# E16-02-002.net
KiCad netlist of a schematic drawn in Altium Designer
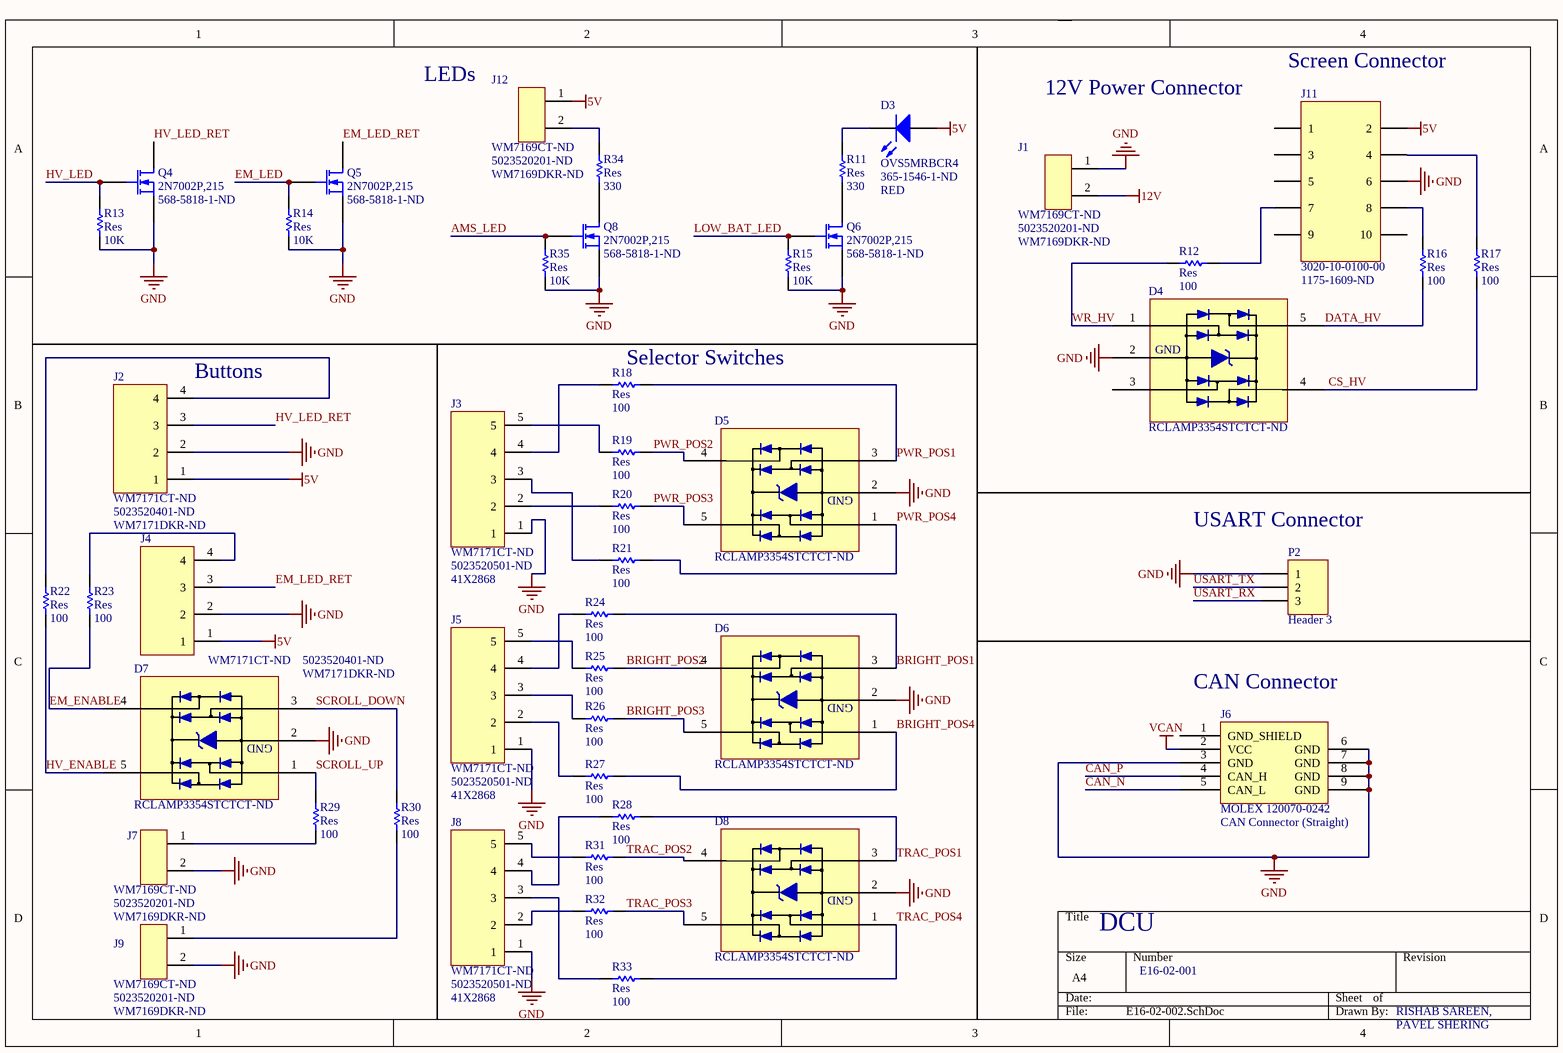
[diagram p0: E16-02-002.SchDoc]

(export (version "E")
  (design (tool "Eeschema 10.0.6"))
  (components
    (comp (ref "D3")
      (value "OVS5MRBCR4")
      (footprint "OVS5MRBCR4")
      (description "Typical RED LED")
      (fields
        (field (name "SUPPLIER PART NUMBER 1") "365-1546-1-ND")
        (field (name "COLOUR") "RED")
        (field (name "PUBLISHER") "Altium Limited")
      )
      (libsource (lib "LEDs") (part "OVS5MRBCR4"))
    )
    (comp (ref "D4")
      (value "RCLAMP3354S.TCT")
      (footprint "SOT95P280X145-5N")
      (description "TVS DIODE 3.3VWM 16VC")
      (fields (field (name "SUPPLIER PART NUMBER 1") "RCLAMP3354STCTCT-ND"))
      (libsource (lib "Diodes") (part "RCLAMP3354S.TCT"))
    )
    (comp (ref "D5")
      (value "RCLAMP3354S.TCT")
      (footprint "SOT95P280X145-5N")
      (description "TVS DIODE 3.3VWM 16VC")
      (fields (field (name "SUPPLIER PART NUMBER 1") "RCLAMP3354STCTCT-ND"))
      (libsource (lib "Diodes") (part "RCLAMP3354S.TCT"))
    )
    (comp (ref "D6")
      (value "RCLAMP3354S.TCT")
      (footprint "SOT95P280X145-5N")
      (description "TVS DIODE 3.3VWM 16VC")
      (fields (field (name "SUPPLIER PART NUMBER 1") "RCLAMP3354STCTCT-ND"))
      (libsource (lib "Diodes") (part "RCLAMP3354S.TCT"))
    )
    (comp (ref "D7")
      (value "RCLAMP3354S.TCT")
      (footprint "SOT95P280X145-5N")
      (description "TVS DIODE 3.3VWM 16VC")
      (fields (field (name "SUPPLIER PART NUMBER 1") "RCLAMP3354STCTCT-ND"))
      (libsource (lib "Diodes") (part "RCLAMP3354S.TCT"))
    )
    (comp (ref "D8")
      (value "RCLAMP3354S.TCT")
      (footprint "SOT95P280X145-5N")
      (description "TVS DIODE 3.3VWM 16VC")
      (fields (field (name "SUPPLIER PART NUMBER 1") "RCLAMP3354STCTCT-ND"))
      (libsource (lib "Diodes") (part "RCLAMP3354S.TCT"))
    )
    (comp (ref "J1")
      (value "J_5023520200")
      (footprint "MOLEX_DURACLIK_2")
      (description "MOLEX DURACLIK 2-PIN RA")
      (fields
        (field (name "SUPPLIER PART NUMBER 1") "5023520201-ND")
        (field (name "SUPPLIER PART NUMBER 2") "WM7169DKR-ND")
      )
      (libsource (lib "Molex_DuraClik") (part "J_5023520200"))
    )
    (comp (ref "J2")
      (value "WM7171CT-ND")
      (footprint "MOLEX_DURACLIK_4")
      (description "MOLEX DURACLIK 4-PIN RA")
      (fields
        (field (name "DIGIKEY_PN") "WM7171CT-ND")
        (field (name "SUPPLIER PART NUMBER 1") "5023520401-ND")
        (field (name "SUPPLIER PART NUMBER 2") "WM7171DKR-ND")
      )
      (libsource (lib "Molex_DuraClik") (part "J_5023520400"))
    )
    (comp (ref "J3")
      (value "WM7171CT-ND")
      (footprint "MOLEX_DURACLIK_5")
      (description "MOLEX DURACLIK 5-PIN RA")
      (fields
        (field (name "DIGIKEY_PN") "WM7171CT-ND")
        (field (name "SUPPLIER PART NUMBER 1") "5023520501-ND")
        (field (name "SUPPLIER PART NUMBER 2") "41X2868")
      )
      (libsource (lib "Molex_DuraClik") (part "J_5023520500"))
    )
    (comp (ref "J4")
      (value "WM7171CT-ND")
      (footprint "MOLEX_DURACLIK_4")
      (description "MOLEX DURACLIK 4-PIN RA")
      (fields
        (field (name "DIGIKEY_PN") "WM7171CT-ND")
        (field (name "SUPPLIER PART NUMBER 1") "5023520401-ND")
        (field (name "SUPPLIER PART NUMBER 2") "WM7171DKR-ND")
      )
      (libsource (lib "Molex_DuraClik") (part "J_5023520400"))
    )
    (comp (ref "J5")
      (value "WM7171CT-ND")
      (footprint "MOLEX_DURACLIK_5")
      (description "MOLEX DURACLIK 5-PIN RA")
      (fields
        (field (name "DIGIKEY_PN") "WM7171CT-ND")
        (field (name "SUPPLIER PART NUMBER 1") "5023520501-ND")
        (field (name "SUPPLIER PART NUMBER 2") "41X2868")
      )
      (libsource (lib "Molex_DuraClik") (part "J_5023520500"))
    )
    (comp (ref "J6")
      (value "CAN Connector (Straight)")
      (footprint "CAN Connector (Straight)")
      (libsource (lib "Molex_CAN_Connector") (part "CAN Connector (Straight)"))
    )
    (comp (ref "J7")
      (value "J_5023520200")
      (footprint "MOLEX_DURACLIK_2")
      (description "MOLEX DURACLIK 2-PIN RA")
      (fields
        (field (name "SUPPLIER PART NUMBER 1") "5023520201-ND")
        (field (name "SUPPLIER PART NUMBER 2") "WM7169DKR-ND")
      )
      (libsource (lib "Molex_DuraClik") (part "J_5023520200"))
    )
    (comp (ref "J8")
      (value "WM7171CT-ND")
      (footprint "MOLEX_DURACLIK_5")
      (description "MOLEX DURACLIK 5-PIN RA")
      (fields
        (field (name "DIGIKEY_PN") "WM7171CT-ND")
        (field (name "SUPPLIER PART NUMBER 1") "5023520501-ND")
        (field (name "SUPPLIER PART NUMBER 2") "41X2868")
      )
      (libsource (lib "Molex_DuraClik") (part "J_5023520500"))
    )
    (comp (ref "J9")
      (value "J_5023520200")
      (footprint "MOLEX_DURACLIK_2")
      (description "MOLEX DURACLIK 2-PIN RA")
      (fields
        (field (name "SUPPLIER PART NUMBER 1") "5023520201-ND")
        (field (name "SUPPLIER PART NUMBER 2") "WM7169DKR-ND")
      )
      (libsource (lib "Molex_DuraClik") (part "J_5023520200"))
    )
    (comp (ref "J11")
      (value "3020-10-0100-00")
      (footprint "IDC 10 Pos")
      (fields (field (name "SUPPLIER PART NUMBER 1") "1175-1609-ND"))
      (libsource (lib "Connectors and Headers") (part "IDC_10Pos"))
    )
    (comp (ref "J12")
      (value "J_5023520200")
      (footprint "MOLEX_DURACLIK_2")
      (description "MOLEX DURACLIK 2-PIN RA")
      (fields
        (field (name "SUPPLIER PART NUMBER 1") "5023520201-ND")
        (field (name "SUPPLIER PART NUMBER 2") "WM7169DKR-ND")
      )
      (libsource (lib "Molex_DuraClik") (part "J_5023520200"))
    )
    (comp (ref "P2")
      (value "Header 3")
      (footprint "HDR1X3")
      (description "Header, 3-Pin")
      (fields (field (name "PUBLISHER") "Altium Limited"))
      (libsource (lib "Connectors and Headers") (part "Header 3"))
    )
    (comp (ref "Q4")
      (value "2N7002P,215")
      (footprint "SOT23-3")
      (description "N-Channel Enhancement Mode Vertical DMOS FET")
      (fields (field (name "SUPPLIER PART NUMBER 1") "568-5818-1-ND"))
      (libsource (lib "Transistors") (part "2N7002P,215"))
    )
    (comp (ref "Q5")
      (value "2N7002P,215")
      (footprint "SOT23-3")
      (description "N-Channel Enhancement Mode Vertical DMOS FET")
      (fields (field (name "SUPPLIER PART NUMBER 1") "568-5818-1-ND"))
      (libsource (lib "Transistors") (part "2N7002P,215"))
    )
    (comp (ref "Q6")
      (value "2N7002P,215")
      (footprint "SOT23-3")
      (description "N-Channel Enhancement Mode Vertical DMOS FET")
      (fields (field (name "SUPPLIER PART NUMBER 1") "568-5818-1-ND"))
      (libsource (lib "Transistors") (part "2N7002P,215"))
    )
    (comp (ref "Q8")
      (value "2N7002P,215")
      (footprint "SOT23-3")
      (description "N-Channel Enhancement Mode Vertical DMOS FET")
      (fields (field (name "SUPPLIER PART NUMBER 1") "568-5818-1-ND"))
      (libsource (lib "Transistors") (part "2N7002P,215"))
    )
    (comp (ref "R11")
      (value "Res")
      (footprint "3216[1206]")
      (description "Surface Mount Resistor")
      (fields (field (name "ALTIUM_VALUE") "330") (field (name "PUBLISHER") "Altium Limited"))
      (libsource (lib "Resistors") (part "Res"))
    )
    (comp (ref "R12")
      (value "Res")
      (footprint "3216[1206]")
      (description "Surface Mount Resistor")
      (fields (field (name "ALTIUM_VALUE") "100") (field (name "PUBLISHER") "Altium Limited"))
      (libsource (lib "Resistors") (part "Res"))
    )
    (comp (ref "R13")
      (value "Res")
      (footprint "3216[1206]")
      (description "Surface Mount Resistor")
      (fields (field (name "ALTIUM_VALUE") "10K") (field (name "PUBLISHER") "Altium Limited"))
      (libsource (lib "Resistors") (part "Res"))
    )
    (comp (ref "R14")
      (value "Res")
      (footprint "3216[1206]")
      (description "Surface Mount Resistor")
      (fields (field (name "ALTIUM_VALUE") "10K") (field (name "PUBLISHER") "Altium Limited"))
      (libsource (lib "Resistors") (part "Res"))
    )
    (comp (ref "R15")
      (value "Res")
      (footprint "3216[1206]")
      (description "Surface Mount Resistor")
      (fields (field (name "ALTIUM_VALUE") "10K") (field (name "PUBLISHER") "Altium Limited"))
      (libsource (lib "Resistors") (part "Res"))
    )
    (comp (ref "R16")
      (value "Res")
      (footprint "3216[1206]")
      (description "Surface Mount Resistor")
      (fields (field (name "ALTIUM_VALUE") "100") (field (name "PUBLISHER") "Altium Limited"))
      (libsource (lib "Resistors") (part "Res"))
    )
    (comp (ref "R17")
      (value "Res")
      (footprint "3216[1206]")
      (description "Surface Mount Resistor")
      (fields (field (name "ALTIUM_VALUE") "100") (field (name "PUBLISHER") "Altium Limited"))
      (libsource (lib "Resistors") (part "Res"))
    )
    (comp (ref "R18")
      (value "Res")
      (footprint "3216[1206]")
      (description "Surface Mount Resistor")
      (fields (field (name "ALTIUM_VALUE") "100") (field (name "PUBLISHER") "Altium Limited"))
      (libsource (lib "Resistors") (part "Res"))
    )
    (comp (ref "R19")
      (value "Res")
      (footprint "3216[1206]")
      (description "Surface Mount Resistor")
      (fields (field (name "ALTIUM_VALUE") "100") (field (name "PUBLISHER") "Altium Limited"))
      (libsource (lib "Resistors") (part "Res"))
    )
    (comp (ref "R20")
      (value "Res")
      (footprint "3216[1206]")
      (description "Surface Mount Resistor")
      (fields (field (name "ALTIUM_VALUE") "100") (field (name "PUBLISHER") "Altium Limited"))
      (libsource (lib "Resistors") (part "Res"))
    )
    (comp (ref "R21")
      (value "Res")
      (footprint "3216[1206]")
      (description "Surface Mount Resistor")
      (fields (field (name "ALTIUM_VALUE") "100") (field (name "PUBLISHER") "Altium Limited"))
      (libsource (lib "Resistors") (part "Res"))
    )
    (comp (ref "R22")
      (value "Res")
      (footprint "3216[1206]")
      (description "Surface Mount Resistor")
      (fields (field (name "ALTIUM_VALUE") "100") (field (name "PUBLISHER") "Altium Limited"))
      (libsource (lib "Resistors") (part "Res"))
    )
    (comp (ref "R23")
      (value "Res")
      (footprint "3216[1206]")
      (description "Surface Mount Resistor")
      (fields (field (name "ALTIUM_VALUE") "100") (field (name "PUBLISHER") "Altium Limited"))
      (libsource (lib "Resistors") (part "Res"))
    )
    (comp (ref "R24")
      (value "Res")
      (footprint "3216[1206]")
      (description "Surface Mount Resistor")
      (fields (field (name "ALTIUM_VALUE") "100") (field (name "PUBLISHER") "Altium Limited"))
      (libsource (lib "Resistors") (part "Res"))
    )
    (comp (ref "R25")
      (value "Res")
      (footprint "3216[1206]")
      (description "Surface Mount Resistor")
      (fields (field (name "ALTIUM_VALUE") "100") (field (name "PUBLISHER") "Altium Limited"))
      (libsource (lib "Resistors") (part "Res"))
    )
    (comp (ref "R26")
      (value "Res")
      (footprint "3216[1206]")
      (description "Surface Mount Resistor")
      (fields (field (name "ALTIUM_VALUE") "100") (field (name "PUBLISHER") "Altium Limited"))
      (libsource (lib "Resistors") (part "Res"))
    )
    (comp (ref "R27")
      (value "Res")
      (footprint "3216[1206]")
      (description "Surface Mount Resistor")
      (fields (field (name "ALTIUM_VALUE") "100") (field (name "PUBLISHER") "Altium Limited"))
      (libsource (lib "Resistors") (part "Res"))
    )
    (comp (ref "R28")
      (value "Res")
      (footprint "3216[1206]")
      (description "Surface Mount Resistor")
      (fields (field (name "ALTIUM_VALUE") "100") (field (name "PUBLISHER") "Altium Limited"))
      (libsource (lib "Resistors") (part "Res"))
    )
    (comp (ref "R29")
      (value "Res")
      (footprint "3216[1206]")
      (description "Surface Mount Resistor")
      (fields (field (name "ALTIUM_VALUE") "100") (field (name "PUBLISHER") "Altium Limited"))
      (libsource (lib "Resistors") (part "Res"))
    )
    (comp (ref "R30")
      (value "Res")
      (footprint "3216[1206]")
      (description "Surface Mount Resistor")
      (fields (field (name "ALTIUM_VALUE") "100") (field (name "PUBLISHER") "Altium Limited"))
      (libsource (lib "Resistors") (part "Res"))
    )
    (comp (ref "R31")
      (value "Res")
      (footprint "3216[1206]")
      (description "Surface Mount Resistor")
      (fields (field (name "ALTIUM_VALUE") "100") (field (name "PUBLISHER") "Altium Limited"))
      (libsource (lib "Resistors") (part "Res"))
    )
    (comp (ref "R32")
      (value "Res")
      (footprint "3216[1206]")
      (description "Surface Mount Resistor")
      (fields (field (name "ALTIUM_VALUE") "100") (field (name "PUBLISHER") "Altium Limited"))
      (libsource (lib "Resistors") (part "Res"))
    )
    (comp (ref "R33")
      (value "Res")
      (footprint "3216[1206]")
      (description "Surface Mount Resistor")
      (fields (field (name "ALTIUM_VALUE") "100") (field (name "PUBLISHER") "Altium Limited"))
      (libsource (lib "Resistors") (part "Res"))
    )
    (comp (ref "R34")
      (value "Res")
      (footprint "3216[1206]")
      (description "Surface Mount Resistor")
      (fields (field (name "ALTIUM_VALUE") "330") (field (name "PUBLISHER") "Altium Limited"))
      (libsource (lib "Resistors") (part "Res"))
    )
    (comp (ref "R35")
      (value "Res")
      (footprint "3216[1206]")
      (description "Surface Mount Resistor")
      (fields (field (name "ALTIUM_VALUE") "10K") (field (name "PUBLISHER") "Altium Limited"))
      (libsource (lib "Resistors") (part "Res"))
    )
  )
  (nets
    (net (code "1") (name "/AMS_LED") (class "Default")
      (node (ref "Q8") (pin "1") (pinfunction "G_1") (pintype "passive"))
      (node (ref "R35") (pin "2") (pinfunction "2_2") (pintype "passive"))
    )
    (net (code "2") (name "/BRIGHT_POS1") (class "Default")
      (node (ref "D6") (pin "3") (pinfunction "3_3") (pintype "passive"))
      (node (ref "R24") (pin "1") (pinfunction "1_1") (pintype "passive"))
    )
    (net (code "3") (name "/BRIGHT_POS2") (class "Default")
      (node (ref "D6") (pin "4") (pinfunction "4_4") (pintype "passive"))
      (node (ref "R25") (pin "2") (pinfunction "2_2") (pintype "passive"))
    )
    (net (code "4") (name "/BRIGHT_POS3") (class "Default")
      (node (ref "D6") (pin "5") (pinfunction "5_5") (pintype "passive"))
      (node (ref "R26") (pin "2") (pinfunction "2_2") (pintype "passive"))
    )
    (net (code "5") (name "/BRIGHT_POS4") (class "Default")
      (node (ref "D6") (pin "1") (pinfunction "1_1") (pintype "passive"))
      (node (ref "R27") (pin "1") (pinfunction "1_1") (pintype "passive"))
    )
    (net (code "6") (name "/CAN_N") (class "Default")
      (node (ref "J6") (pin "5") (pinfunction "CAN_L_5") (pintype "passive"))
    )
    (net (code "7") (name "/CAN_P") (class "Default")
      (node (ref "J6") (pin "4") (pinfunction "CAN_H_4") (pintype "passive"))
    )
    (net (code "8") (name "/CS_HV") (class "Default")
      (node (ref "D4") (pin "4") (pinfunction "4_4") (pintype "passive"))
      (node (ref "R17") (pin "1") (pinfunction "1_1") (pintype "passive"))
    )
    (net (code "9") (name "/DATA_HV") (class "Default")
      (node (ref "D4") (pin "5") (pinfunction "5_5") (pintype "passive"))
      (node (ref "R16") (pin "1") (pinfunction "1_1") (pintype "passive"))
    )
    (net (code "10") (name "/EM_ENABLE") (class "Default")
      (node (ref "D7") (pin "4") (pinfunction "4_4") (pintype "passive"))
      (node (ref "R23") (pin "1") (pinfunction "1_1") (pintype "passive"))
    )
    (net (code "11") (name "/EM_LED") (class "Default")
      (node (ref "Q5") (pin "1") (pinfunction "G_1") (pintype "passive"))
      (node (ref "R14") (pin "2") (pinfunction "2_2") (pintype "passive"))
    )
    (net (code "12") (name "/EM_LED_RET") (class "Default")
      (node (ref "J4") (pin "3") (pinfunction "3_3") (pintype "passive"))
      (node (ref "Q5") (pin "3") (pinfunction "D_3") (pintype "passive"))
    )
    (net (code "13") (name "/HV_ENABLE") (class "Default")
      (node (ref "D7") (pin "5") (pinfunction "5_5") (pintype "passive"))
      (node (ref "R22") (pin "1") (pinfunction "1_1") (pintype "passive"))
    )
    (net (code "14") (name "/HV_LED") (class "Default")
      (node (ref "Q4") (pin "1") (pinfunction "G_1") (pintype "passive"))
      (node (ref "R13") (pin "2") (pinfunction "2_2") (pintype "passive"))
    )
    (net (code "15") (name "/HV_LED_RET") (class "Default")
      (node (ref "J2") (pin "3") (pinfunction "3_3") (pintype "passive"))
      (node (ref "Q4") (pin "3") (pinfunction "D_3") (pintype "passive"))
    )
    (net (code "16") (name "/LOW_BAT_LED") (class "Default")
      (node (ref "Q6") (pin "1") (pinfunction "G_1") (pintype "passive"))
      (node (ref "R15") (pin "2") (pinfunction "2_2") (pintype "passive"))
    )
    (net (code "17") (name "/PWR_POS1") (class "Default")
      (node (ref "D5") (pin "3") (pinfunction "3_3") (pintype "passive"))
      (node (ref "R18") (pin "1") (pinfunction "1_1") (pintype "passive"))
    )
    (net (code "18") (name "/PWR_POS2") (class "Default")
      (node (ref "D5") (pin "4") (pinfunction "4_4") (pintype "passive"))
      (node (ref "R19") (pin "1") (pinfunction "1_1") (pintype "passive"))
    )
    (net (code "19") (name "/PWR_POS3") (class "Default")
      (node (ref "D5") (pin "5") (pinfunction "5_5") (pintype "passive"))
      (node (ref "R20") (pin "2") (pinfunction "2_2") (pintype "passive"))
    )
    (net (code "20") (name "/PWR_POS4") (class "Default")
      (node (ref "D5") (pin "1") (pinfunction "1_1") (pintype "passive"))
      (node (ref "R21") (pin "1") (pinfunction "1_1") (pintype "passive"))
    )
    (net (code "21") (name "/SCROLL_DOWN") (class "Default")
      (node (ref "D7") (pin "3") (pinfunction "3_3") (pintype "passive"))
      (node (ref "R30") (pin "2") (pinfunction "2_2") (pintype "passive"))
    )
    (net (code "22") (name "/SCROLL_UP") (class "Default")
      (node (ref "D7") (pin "1") (pinfunction "1_1") (pintype "passive"))
      (node (ref "R29") (pin "1") (pinfunction "1_1") (pintype "passive"))
    )
    (net (code "23") (name "/TRAC_POS1") (class "Default")
      (node (ref "D8") (pin "3") (pinfunction "3_3") (pintype "passive"))
      (node (ref "R28") (pin "1") (pinfunction "1_1") (pintype "passive"))
    )
    (net (code "24") (name "/TRAC_POS2") (class "Default")
      (node (ref "D8") (pin "4") (pinfunction "4_4") (pintype "passive"))
      (node (ref "R31") (pin "2") (pinfunction "2_2") (pintype "passive"))
    )
    (net (code "25") (name "/TRAC_POS3") (class "Default")
      (node (ref "D8") (pin "5") (pinfunction "5_5") (pintype "passive"))
      (node (ref "R32") (pin "2") (pinfunction "2_2") (pintype "passive"))
    )
    (net (code "26") (name "/TRAC_POS4") (class "Default")
      (node (ref "D8") (pin "1") (pinfunction "1_1") (pintype "passive"))
      (node (ref "R33") (pin "1") (pinfunction "1_1") (pintype "passive"))
    )
    (net (code "27") (name "/USART_RX") (class "Default")
      (node (ref "P2") (pin "3") (pinfunction "3_3") (pintype "passive"))
    )
    (net (code "28") (name "/USART_TX") (class "Default")
      (node (ref "P2") (pin "2") (pinfunction "2_2") (pintype "passive"))
    )
    (net (code "29") (name "/WR_HV") (class "Default")
      (node (ref "D4") (pin "1") (pinfunction "1_1") (pintype "passive"))
      (node (ref "R12") (pin "1") (pinfunction "1_1") (pintype "passive"))
    )
    (net (code "30") (name "5V") (class "Default")
      (node (ref "D3") (pin "1") (pinfunction "A_1") (pintype "passive"))
      (node (ref "J11") (pin "2") (pinfunction "2_2") (pintype "passive"))
      (node (ref "J12") (pin "1") (pinfunction "1_1") (pintype "passive"))
      (node (ref "J2") (pin "1") (pinfunction "1_1") (pintype "passive"))
      (node (ref "J4") (pin "1") (pinfunction "1_1") (pintype "passive"))
    )
    (net (code "31") (name "12V") (class "Default")
      (node (ref "J1") (pin "2") (pinfunction "2_2") (pintype "passive"))
    )
    (net (code "32") (name "GND") (class "Default")
      (node (ref "D4") (pin "2") (pinfunction "GND_2") (pintype "passive"))
      (node (ref "D5") (pin "2") (pinfunction "GND_2") (pintype "passive"))
      (node (ref "D6") (pin "2") (pinfunction "GND_2") (pintype "passive"))
      (node (ref "D7") (pin "2") (pinfunction "GND_2") (pintype "passive"))
      (node (ref "D8") (pin "2") (pinfunction "GND_2") (pintype "passive"))
      (node (ref "J1") (pin "1") (pinfunction "1_1") (pintype "passive"))
      (node (ref "J11") (pin "6") (pinfunction "6_6") (pintype "passive"))
      (node (ref "J2") (pin "2") (pinfunction "2_2") (pintype "passive"))
      (node (ref "J3") (pin "1") (pinfunction "1_1") (pintype "passive"))
      (node (ref "J4") (pin "2") (pinfunction "2_2") (pintype "passive"))
      (node (ref "J5") (pin "1") (pinfunction "1_1") (pintype "passive"))
      (node (ref "J6") (pin "3") (pinfunction "GND_3") (pintype "passive"))
      (node (ref "J6") (pin "6") (pinfunction "GND_6") (pintype "passive"))
      (node (ref "J6") (pin "7") (pinfunction "GND_7") (pintype "passive"))
      (node (ref "J6") (pin "8") (pinfunction "GND_8") (pintype "passive"))
      (node (ref "J6") (pin "9") (pinfunction "GND_9") (pintype "passive"))
      (node (ref "J7") (pin "2") (pinfunction "2_2") (pintype "passive"))
      (node (ref "J8") (pin "1") (pinfunction "1_1") (pintype "passive"))
      (node (ref "J9") (pin "2") (pinfunction "2_2") (pintype "passive"))
      (node (ref "P2") (pin "1") (pinfunction "1_1") (pintype "passive"))
      (node (ref "Q4") (pin "2") (pinfunction "S_2") (pintype "passive"))
      (node (ref "Q5") (pin "2") (pinfunction "S_2") (pintype "passive"))
      (node (ref "Q6") (pin "2") (pinfunction "S_2") (pintype "passive"))
      (node (ref "Q8") (pin "2") (pinfunction "S_2") (pintype "passive"))
      (node (ref "R13") (pin "1") (pinfunction "1_1") (pintype "passive"))
      (node (ref "R14") (pin "1") (pinfunction "1_1") (pintype "passive"))
      (node (ref "R15") (pin "1") (pinfunction "1_1") (pintype "passive"))
      (node (ref "R35") (pin "1") (pinfunction "1_1") (pintype "passive"))
    )
    (net (code "33") (name "Net-(D3-K)") (class "Default")
      (node (ref "D3") (pin "2") (pinfunction "K_2") (pintype "passive"))
      (node (ref "R11") (pin "2") (pinfunction "2_2") (pintype "passive"))
    )
    (net (code "34") (name "Net-(J2-Pad4)") (class "Default")
      (node (ref "J2") (pin "4") (pinfunction "4_4") (pintype "passive"))
      (node (ref "R22") (pin "2") (pinfunction "2_2") (pintype "passive"))
    )
    (net (code "35") (name "Net-(J3-Pad2)") (class "Default")
      (node (ref "J3") (pin "2") (pinfunction "2_2") (pintype "passive"))
      (node (ref "R20") (pin "1") (pinfunction "1_1") (pintype "passive"))
    )
    (net (code "36") (name "Net-(J3-Pad3)") (class "Default")
      (node (ref "J3") (pin "3") (pinfunction "3_3") (pintype "passive"))
      (node (ref "R21") (pin "2") (pinfunction "2_2") (pintype "passive"))
    )
    (net (code "37") (name "Net-(J3-Pad4)") (class "Default")
      (node (ref "J3") (pin "4") (pinfunction "4_4") (pintype "passive"))
      (node (ref "R18") (pin "2") (pinfunction "2_2") (pintype "passive"))
    )
    (net (code "38") (name "Net-(J3-Pad5)") (class "Default")
      (node (ref "J3") (pin "5") (pinfunction "5_5") (pintype "passive"))
      (node (ref "R19") (pin "2") (pinfunction "2_2") (pintype "passive"))
    )
    (net (code "39") (name "Net-(J4-Pad4)") (class "Default")
      (node (ref "J4") (pin "4") (pinfunction "4_4") (pintype "passive"))
      (node (ref "R23") (pin "2") (pinfunction "2_2") (pintype "passive"))
    )
    (net (code "40") (name "Net-(J5-Pad2)") (class "Default")
      (node (ref "J5") (pin "2") (pinfunction "2_2") (pintype "passive"))
      (node (ref "R27") (pin "2") (pinfunction "2_2") (pintype "passive"))
    )
    (net (code "41") (name "Net-(J5-Pad3)") (class "Default")
      (node (ref "J5") (pin "3") (pinfunction "3_3") (pintype "passive"))
      (node (ref "R26") (pin "1") (pinfunction "1_1") (pintype "passive"))
    )
    (net (code "42") (name "Net-(J5-Pad4)") (class "Default")
      (node (ref "J5") (pin "4") (pinfunction "4_4") (pintype "passive"))
      (node (ref "R24") (pin "2") (pinfunction "2_2") (pintype "passive"))
    )
    (net (code "43") (name "Net-(J5-Pad5)") (class "Default")
      (node (ref "J5") (pin "5") (pinfunction "5_5") (pintype "passive"))
      (node (ref "R25") (pin "1") (pinfunction "1_1") (pintype "passive"))
    )
    (net (code "44") (name "Net-(J7-Pad1)") (class "Default")
      (node (ref "J7") (pin "1") (pinfunction "1_1") (pintype "passive"))
      (node (ref "R29") (pin "2") (pinfunction "2_2") (pintype "passive"))
    )
    (net (code "45") (name "Net-(J8-Pad2)") (class "Default")
      (node (ref "J8") (pin "2") (pinfunction "2_2") (pintype "passive"))
      (node (ref "R32") (pin "1") (pinfunction "1_1") (pintype "passive"))
    )
    (net (code "46") (name "Net-(J8-Pad3)") (class "Default")
      (node (ref "J8") (pin "3") (pinfunction "3_3") (pintype "passive"))
      (node (ref "R33") (pin "2") (pinfunction "2_2") (pintype "passive"))
    )
    (net (code "47") (name "Net-(J8-Pad4)") (class "Default")
      (node (ref "J8") (pin "4") (pinfunction "4_4") (pintype "passive"))
      (node (ref "R28") (pin "2") (pinfunction "2_2") (pintype "passive"))
    )
    (net (code "48") (name "Net-(J8-Pad5)") (class "Default")
      (node (ref "J8") (pin "5") (pinfunction "5_5") (pintype "passive"))
      (node (ref "R31") (pin "1") (pinfunction "1_1") (pintype "passive"))
    )
    (net (code "49") (name "Net-(J9-Pad1)") (class "Default")
      (node (ref "J9") (pin "1") (pinfunction "1_1") (pintype "passive"))
      (node (ref "R30") (pin "1") (pinfunction "1_1") (pintype "passive"))
    )
    (net (code "50") (name "Net-(J11-Pad4)") (class "Default")
      (node (ref "J11") (pin "4") (pinfunction "4_4") (pintype "passive"))
      (node (ref "R17") (pin "2") (pinfunction "2_2") (pintype "passive"))
    )
    (net (code "51") (name "Net-(J11-Pad7)") (class "Default")
      (node (ref "J11") (pin "7") (pinfunction "7_7") (pintype "passive"))
      (node (ref "R12") (pin "2") (pinfunction "2_2") (pintype "passive"))
    )
    (net (code "52") (name "Net-(J11-Pad8)") (class "Default")
      (node (ref "J11") (pin "8") (pinfunction "8_8") (pintype "passive"))
      (node (ref "R16") (pin "2") (pinfunction "2_2") (pintype "passive"))
    )
    (net (code "53") (name "Net-(J12-Pad2)") (class "Default")
      (node (ref "J12") (pin "2") (pinfunction "2_2") (pintype "passive"))
      (node (ref "R34") (pin "2") (pinfunction "2_2") (pintype "passive"))
    )
    (net (code "54") (name "Net-(Q6-D)") (class "Default")
      (node (ref "Q6") (pin "3") (pinfunction "D_3") (pintype "passive"))
      (node (ref "R11") (pin "1") (pinfunction "1_1") (pintype "passive"))
    )
    (net (code "55") (name "Net-(Q8-D)") (class "Default")
      (node (ref "Q8") (pin "3") (pinfunction "D_3") (pintype "passive"))
      (node (ref "R34") (pin "1") (pinfunction "1_1") (pintype "passive"))
    )
    (net (code "56") (name "VCAN") (class "Default")
      (node (ref "J6") (pin "2") (pinfunction "VCC_2") (pintype "passive"))
    )
    (net (code "57") (name "unconnected-(D4-Pad3)") (class "Default")
      (node (ref "D4") (pin "3") (pinfunction "3_3") (pintype "passive"))
    )
    (net (code "58") (name "unconnected-(J6-GND_SHIELD-Pad1)") (class "Default")
      (node (ref "J6") (pin "1") (pinfunction "GND_SHIELD_1") (pintype "passive"))
    )
    (net (code "59") (name "unconnected-(J11-Pad1)") (class "Default")
      (node (ref "J11") (pin "1") (pinfunction "1_1") (pintype "passive"))
    )
    (net (code "60") (name "unconnected-(J11-Pad3)") (class "Default")
      (node (ref "J11") (pin "3") (pinfunction "3_3") (pintype "passive"))
    )
    (net (code "61") (name "unconnected-(J11-Pad5)") (class "Default")
      (node (ref "J11") (pin "5") (pinfunction "5_5") (pintype "passive"))
    )
    (net (code "62") (name "unconnected-(J11-Pad9)") (class "Default")
      (node (ref "J11") (pin "9") (pinfunction "9_9") (pintype "passive"))
    )
    (net (code "63") (name "unconnected-(J11-Pad10)") (class "Default")
      (node (ref "J11") (pin "10") (pinfunction "10_10") (pintype "passive"))
    )
  )
)
